# Feather_Ace_Shield.net
KiCad netlist of a schematic drawn in EAGLE
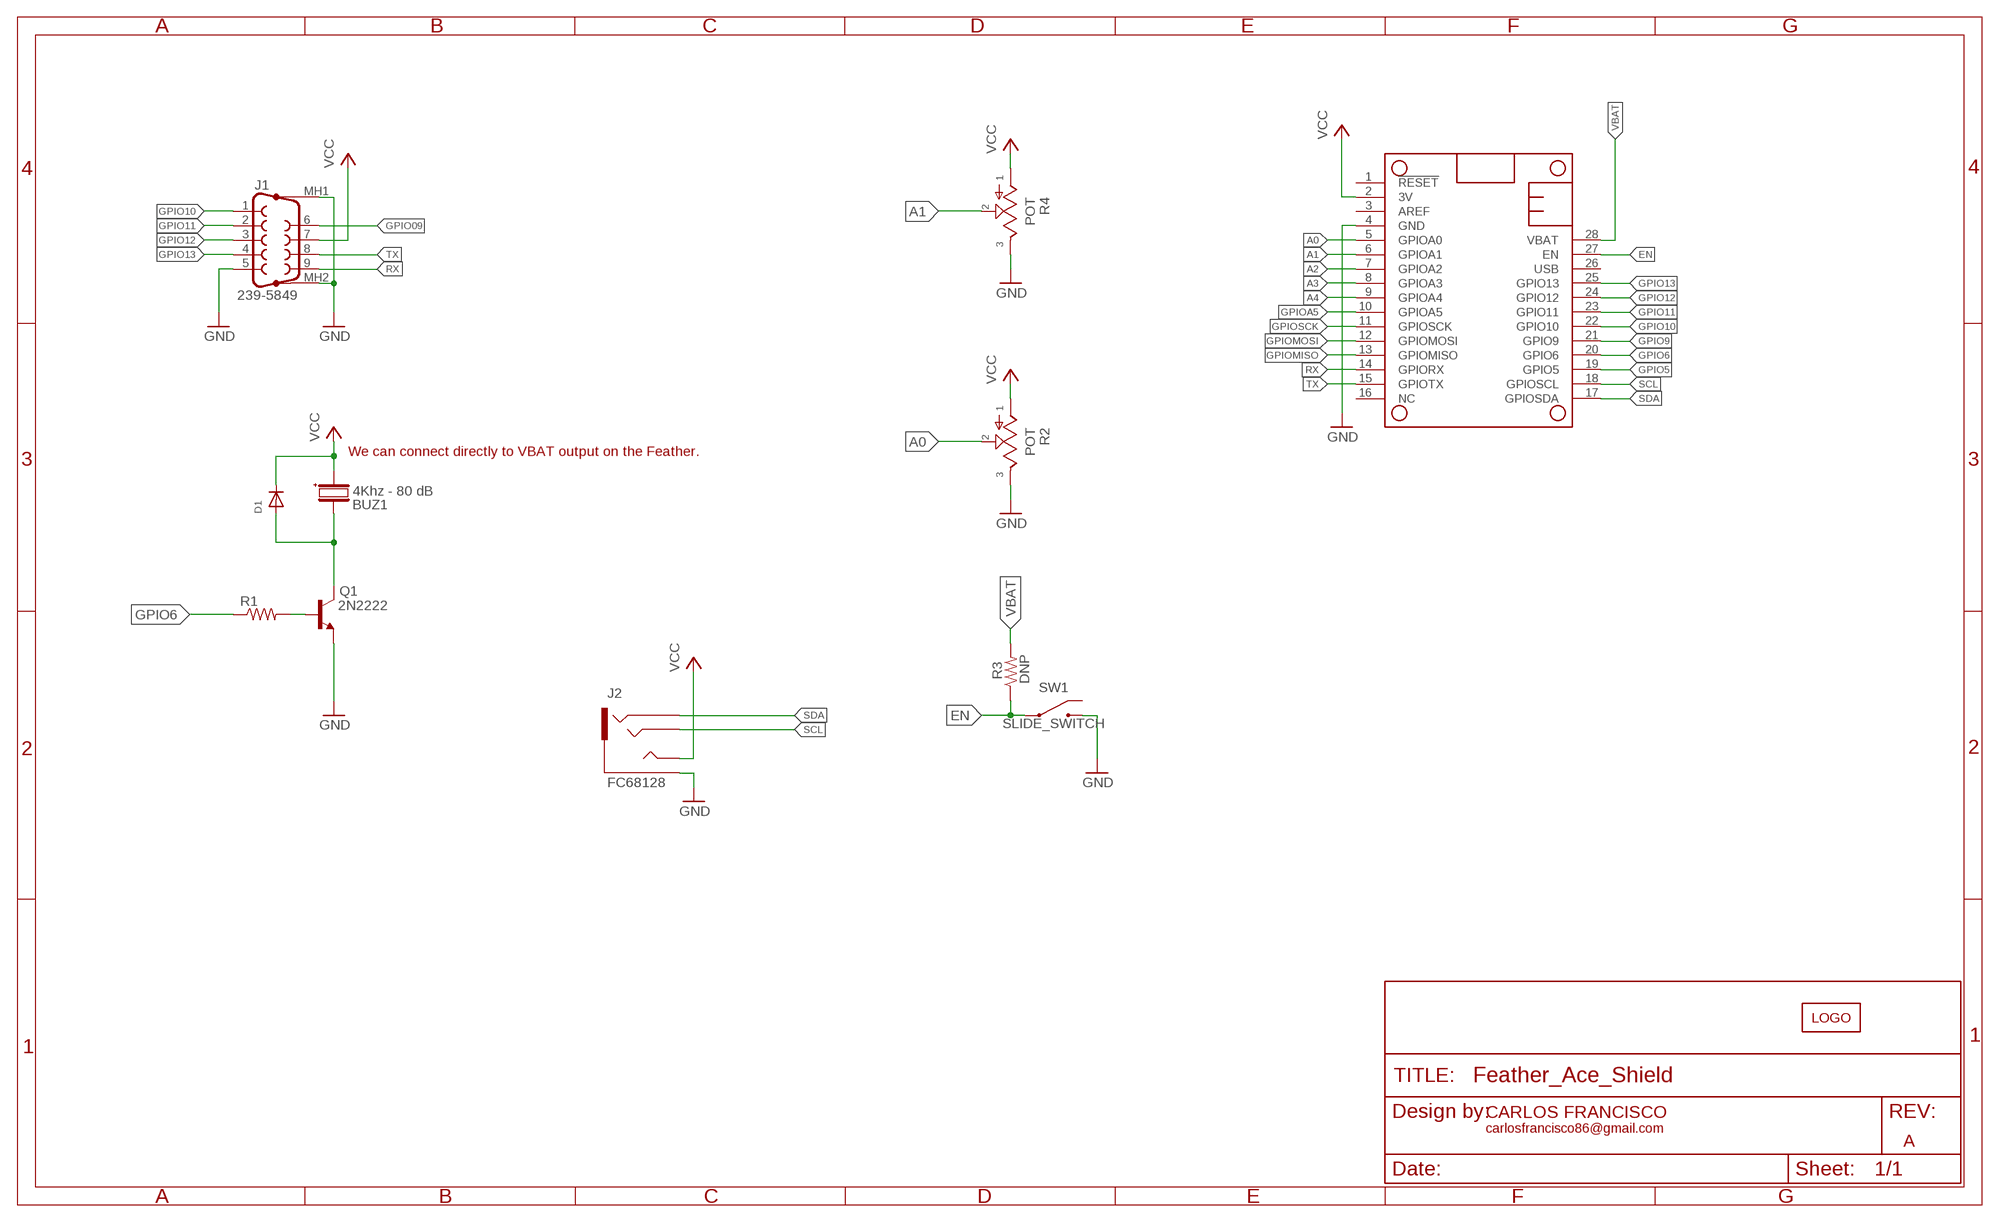
[diagram p0: schematic, sheet 1]

(export (version "E")
  (design (tool "Eeschema 10.0.6"))
  (components
    (comp (ref "BUZ1")
      (value "4Khz - 80 dB")
      (footprint "eagle-import:-511-7620")
      (fields (field (name "MFR") "RS PRO"))
      (libsource (lib "eagle-import") (part "BUZZER-511-7620"))
    )
    (comp (ref "D1")
      (value "DIODEDO-1N4148")
      (footprint "eagle-import:DO-1N4148")
      (libsource (lib "eagle-import") (part "DIODEDO-1N4148"))
    )
    (comp (ref "J1")
      (value "239-5849")
      (footprint "eagle-import:DB9_PLUG")
      (fields (field (name "MFR") "RS Pro"))
      (libsource (lib "eagle-import") (part "DB9_FEMALE-239-5849"))
    )
    (comp (ref "J2")
      (value "FC68128")
      (footprint "eagle-import:FC68128")
      (libsource (lib "eagle-import") (part "3.5MM_JACKFC68128"))
    )
    (comp (ref "MS1")
      (value "FEATHERWING_NODIM")
      (footprint "eagle-import:FEATHERWING_DIM")
      (libsource (lib "eagle-import") (part "FEATHERWING_NODIM"))
    )
    (comp (ref "Q1")
      (value "2N2222")
      (footprint "eagle-import:TO92-EBC-OVAL")
      (libsource (lib "eagle-import") (part "2N2222"))
    )
    (comp (ref "R1")
      (value "R-US_0207/10")
      (footprint "eagle-import:0207_10")
      (libsource (lib "eagle-import") (part "R-US_0207/10"))
    )
    (comp (ref "R2")
      (value "POT")
      (footprint "eagle-import:3386P_1")
      (fields
        (field (name "ARROW_PART_NUMBER") "3386P-1-200LF")
        (field (name "MOUSER_PART_NUMBER") "652-3386P-1-200LF")
      )
      (libsource (lib "eagle-import") (part "POT"))
    )
    (comp (ref "R3")
      (value "DNP")
      (footprint "eagle-import:0207_10")
      (libsource (lib "eagle-import") (part "R-US_0207/10"))
    )
    (comp (ref "R4")
      (value "POT")
      (footprint "eagle-import:3386P_1")
      (fields
        (field (name "ARROW_PART_NUMBER") "3386P-1-200LF")
        (field (name "MOUSER_PART_NUMBER") "652-3386P-1-200LF")
      )
      (libsource (lib "eagle-import") (part "POT"))
    )
    (comp (ref "SW1")
      (value "SLIDE_SWITCH")
      (footprint "eagle-import:OS102011MA1QN1")
      (fields
        (field (name "ARROW_PART_NUMBER") "OS102011MA1QN1")
        (field (name "MOUSER_PART_NUMBER") "611-OS102011MA1QN1")
      )
      (libsource (lib "eagle-import") (part "SLIDE_SWITCH"))
    )
    (comp (ref "U$2")
      (value "LOGO-10MM")
      (footprint "eagle-import:LOGO_10MM")
      (libsource (lib "eagle-import") (part "LOGO-10MM"))
    )
  )
  (nets
    (net (code "1") (name "/USB") (class "Default")
      (node (ref "MS1") (pin "26") (pinfunction "USB_26") (pintype "power_in"))
    )
    (net (code "2") (name "A0") (class "Default")
      (node (ref "MS1") (pin "5") (pinfunction "GPIOA0_5") (pintype "bidirectional"))
      (node (ref "R2") (pin "2") (pinfunction "2_2") (pintype "passive"))
    )
    (net (code "3") (name "A1") (class "Default")
      (node (ref "MS1") (pin "6") (pinfunction "GPIOA1_6") (pintype "bidirectional"))
      (node (ref "R4") (pin "2") (pinfunction "2_2") (pintype "passive"))
    )
    (net (code "4") (name "A2") (class "Default")
      (node (ref "MS1") (pin "7") (pinfunction "GPIOA2_7") (pintype "bidirectional"))
    )
    (net (code "5") (name "A3") (class "Default")
      (node (ref "MS1") (pin "8") (pinfunction "GPIOA3_8") (pintype "bidirectional"))
    )
    (net (code "6") (name "A4") (class "Default")
      (node (ref "MS1") (pin "9") (pinfunction "GPIOA4_9") (pintype "bidirectional"))
    )
    (net (code "7") (name "EN") (class "Default")
      (node (ref "MS1") (pin "27") (pinfunction "EN_27") (pintype "passive"))
      (node (ref "R3") (pin "1") (pinfunction "1_1") (pintype "passive"))
      (node (ref "SW1") (pin "2") (pinfunction "2_2") (pintype "passive"))
    )
    (net (code "8") (name "GND") (class "Default")
      (node (ref "J1") (pin "5") (pinfunction "5_5") (pintype "passive"))
      (node (ref "J1") (pin "MH1") (pinfunction "G1_MH1") (pintype "passive"))
      (node (ref "J1") (pin "MH2") (pinfunction "G2_MH2") (pintype "passive"))
      (node (ref "J2") (pin "1S_L") (pinfunction "1S_SLEEVE_1S_L") (pintype "bidirectional"))
      (node (ref "J2") (pin "1S_R") (pinfunction "1S_SLEEVE_1S_R") (pintype "bidirectional"))
      (node (ref "MS1") (pin "4") (pinfunction "GND_4") (pintype "power_in"))
      (node (ref "Q1") (pin "E") (pinfunction "E_E") (pintype "passive"))
      (node (ref "R2") (pin "3") (pinfunction "3_3") (pintype "passive"))
      (node (ref "R4") (pin "3") (pinfunction "3_3") (pintype "passive"))
      (node (ref "SW1") (pin "1") (pinfunction "1_1") (pintype "passive"))
    )
    (net (code "9") (name "GPIO5") (class "Default")
      (node (ref "MS1") (pin "19") (pinfunction "GPIO5_19") (pintype "bidirectional"))
    )
    (net (code "10") (name "GPIO6") (class "Default")
      (node (ref "MS1") (pin "20") (pinfunction "GPIO6_20") (pintype "bidirectional"))
      (node (ref "R1") (pin "1") (pinfunction "1_1") (pintype "passive"))
    )
    (net (code "11") (name "GPIO09") (class "Default")
      (node (ref "J1") (pin "6") (pinfunction "6_6") (pintype "passive"))
    )
    (net (code "12") (name "GPIO9") (class "Default")
      (node (ref "MS1") (pin "21") (pinfunction "GPIO9_21") (pintype "bidirectional"))
    )
    (net (code "13") (name "GPIO10") (class "Default")
      (node (ref "J1") (pin "1") (pinfunction "1_1") (pintype "passive"))
      (node (ref "MS1") (pin "22") (pinfunction "GPIO10_22") (pintype "bidirectional"))
    )
    (net (code "14") (name "GPIO11") (class "Default")
      (node (ref "J1") (pin "2") (pinfunction "2_2") (pintype "passive"))
      (node (ref "MS1") (pin "23") (pinfunction "GPIO11_23") (pintype "bidirectional"))
    )
    (net (code "15") (name "GPIO12") (class "Default")
      (node (ref "J1") (pin "3") (pinfunction "3_3") (pintype "passive"))
      (node (ref "MS1") (pin "24") (pinfunction "GPIO12_24") (pintype "bidirectional"))
    )
    (net (code "16") (name "GPIO13") (class "Default")
      (node (ref "J1") (pin "4") (pinfunction "4_4") (pintype "passive"))
      (node (ref "MS1") (pin "25") (pinfunction "GPIO13_25") (pintype "bidirectional"))
    )
    (net (code "17") (name "GPIOA5") (class "Default")
      (node (ref "MS1") (pin "10") (pinfunction "GPIOA5_10") (pintype "bidirectional"))
    )
    (net (code "18") (name "GPIOMISO") (class "Default")
      (node (ref "MS1") (pin "13") (pinfunction "GPIOMISO_13") (pintype "bidirectional"))
    )
    (net (code "19") (name "GPIOMOSI") (class "Default")
      (node (ref "MS1") (pin "12") (pinfunction "GPIOMOSI_12") (pintype "bidirectional"))
    )
    (net (code "20") (name "GPIOSCK") (class "Default")
      (node (ref "MS1") (pin "11") (pinfunction "GPIOSCK_11") (pintype "bidirectional"))
    )
    (net (code "21") (name "Net-(BUZ1-Pad-)") (class "Default")
      (node (ref "BUZ1") (pin "-") (pinfunction "-_-") (pintype "passive"))
      (node (ref "D1") (pin "A") (pinfunction "A_A") (pintype "passive"))
      (node (ref "Q1") (pin "C") (pinfunction "C_C") (pintype "passive"))
    )
    (net (code "22") (name "Net-(Q1-PadB)") (class "Default")
      (node (ref "Q1") (pin "B") (pinfunction "B_B") (pintype "passive"))
      (node (ref "R1") (pin "2") (pinfunction "2_2") (pintype "passive"))
    )
    (net (code "23") (name "RX") (class "Default")
      (node (ref "J1") (pin "9") (pinfunction "9_9") (pintype "passive"))
      (node (ref "MS1") (pin "14") (pinfunction "GPIORX_14") (pintype "bidirectional"))
    )
    (net (code "24") (name "SCL") (class "Default")
      (node (ref "J2") (pin "2R") (pinfunction "2R_1RING_2R") (pintype "bidirectional"))
      (node (ref "MS1") (pin "18") (pinfunction "GPIOSCL_18") (pintype "bidirectional"))
    )
    (net (code "25") (name "SDA") (class "Default")
      (node (ref "J2") (pin "6_L") (pinfunction "6SR_2RING_6_L") (pintype "bidirectional"))
      (node (ref "J2") (pin "6_R") (pinfunction "6SR_2RING_6_R") (pintype "bidirectional"))
      (node (ref "MS1") (pin "17") (pinfunction "GPIOSDA_17") (pintype "bidirectional"))
    )
    (net (code "26") (name "TX") (class "Default")
      (node (ref "J1") (pin "8") (pinfunction "8_8") (pintype "passive"))
      (node (ref "MS1") (pin "15") (pinfunction "GPIOTX_15") (pintype "bidirectional"))
    )
    (net (code "27") (name "VBAT") (class "Default")
      (node (ref "MS1") (pin "28") (pinfunction "VBAT_28") (pintype "power_in"))
      (node (ref "R3") (pin "2") (pinfunction "2_2") (pintype "passive"))
    )
    (net (code "28") (name "VCC") (class "Default")
      (node (ref "BUZ1") (pin "+") (pinfunction "+_+") (pintype "passive"))
      (node (ref "D1") (pin "C") (pinfunction "C_C") (pintype "passive"))
      (node (ref "J1") (pin "7") (pinfunction "7_7") (pintype "passive"))
      (node (ref "J2") (pin "3T") (pinfunction "3T_TIP_3T") (pintype "bidirectional"))
      (node (ref "MS1") (pin "2") (pinfunction "3V_2") (pintype "power_in"))
      (node (ref "R2") (pin "1") (pinfunction "1_1") (pintype "passive"))
      (node (ref "R4") (pin "1") (pinfunction "1_1") (pintype "passive"))
    )
    (net (code "29") (name "unconnected-(MS1-AREF-Pad3)") (class "Default")
      (node (ref "MS1") (pin "3") (pinfunction "AREF_3") (pintype "passive"))
    )
    (net (code "30") (name "unconnected-(MS1-NC-Pad16)") (class "Default")
      (node (ref "MS1") (pin "16") (pinfunction "NC_16") (pintype "passive"))
    )
    (net (code "31") (name "unconnected-(MS1-~{RESET}-Pad1)") (class "Default")
      (node (ref "MS1") (pin "1") (pinfunction "~{RESET}_1") (pintype "input"))
    )
    (net (code "32") (name "unconnected-(SW1-Pad3)") (class "Default")
      (node (ref "SW1") (pin "3") (pinfunction "3_3") (pintype "passive"))
    )
  )
)
